# PSU.net
KiCad netlist of a schematic drawn in Altium Designer
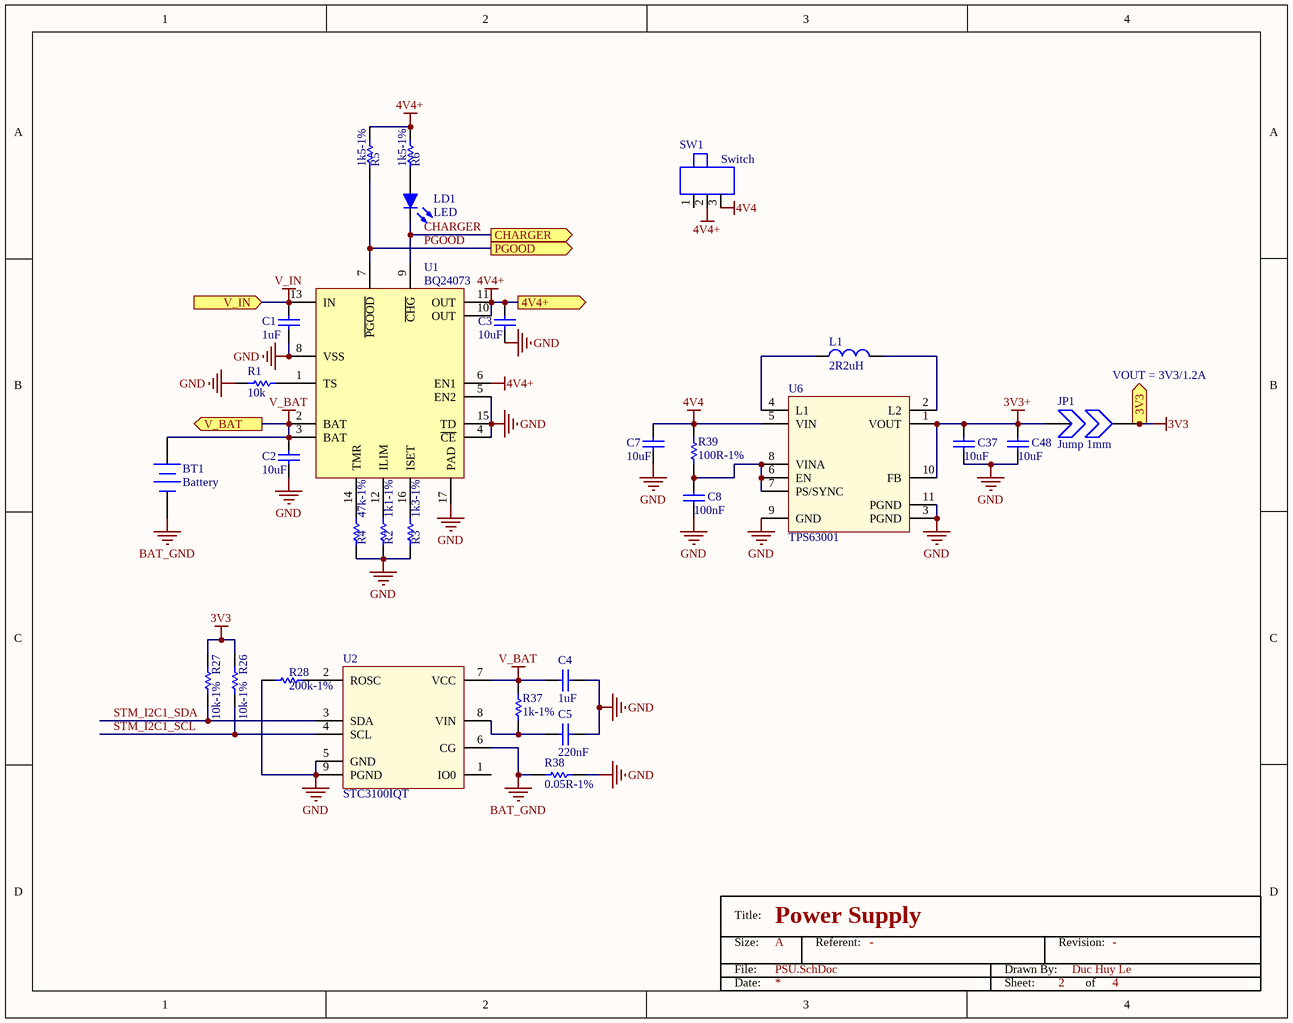
[diagram p0: PSU.SchDoc]

(export (version "E")
  (design (tool "Eeschema 10.0.6"))
  (components
    (comp (ref "BT1")
      (value "Battery")
      (footprint "BAT-2")
      (description "Multicell Battery")
      (fields (field (name "PUBLISHER") "Altium Limited"))
      (libsource (lib "Miscellaneous Devices") (part "Battery"))
    )
    (comp (ref "C1")
      (value "1uF")
      (footprint "Cap 0603")
      (description "Cap SMD")
      (libsource (lib "duchuylee") (part "Cap"))
    )
    (comp (ref "C2")
      (value "10uF")
      (footprint "Cap 0603")
      (description "Cap SMD")
      (libsource (lib "duchuylee") (part "Cap"))
    )
    (comp (ref "C3")
      (value "10uF")
      (footprint "Cap 0603")
      (description "Cap SMD")
      (libsource (lib "duchuylee") (part "Cap"))
    )
    (comp (ref "C4")
      (value "1uF")
      (footprint "Cap 0603")
      (description "Cap SMD")
      (libsource (lib "duchuylee") (part "Cap"))
    )
    (comp (ref "C5")
      (value "220nF")
      (footprint "Cap 0603")
      (description "Cap SMD")
      (libsource (lib "duchuylee") (part "Cap"))
    )
    (comp (ref "C7")
      (value "10uF")
      (footprint "Cap 0603")
      (description "Cap SMD")
      (libsource (lib "duchuylee") (part "Cap"))
    )
    (comp (ref "C8")
      (value "100nF")
      (footprint "Cap 0603")
      (description "Cap SMD")
      (libsource (lib "duchuylee") (part "Cap"))
    )
    (comp (ref "C37")
      (value "10uF")
      (footprint "Cap 0603")
      (description "Cap SMD")
      (libsource (lib "duchuylee") (part "Cap"))
    )
    (comp (ref "C48")
      (value "10uF")
      (footprint "Cap 0603")
      (description "Cap SMD")
      (libsource (lib "duchuylee") (part "Cap"))
    )
    (comp (ref "JP1") (value "Jump 1mm") (footprint "Jump 1mm") (libsource (lib "duchuylee") (part "Jump")))
    (comp (ref "L1")
      (value "2R2uH")
      (footprint "Inductor 0520")
      (description "L- SMD")
      (libsource (lib "duchuylee") (part "Inductor"))
    )
    (comp (ref "LD1") (value "LED") (footprint "LED") (libsource (lib "duchuylee") (part "LED")))
    (comp (ref "R1")
      (value "10k")
      (footprint "Res 0603")
      (description "Res SMD")
      (libsource (lib "duchuylee") (part "Res"))
    )
    (comp (ref "R2")
      (value "1k1-1%")
      (footprint "Res 0603")
      (description "Res SMD")
      (libsource (lib "duchuylee") (part "Res"))
    )
    (comp (ref "R3")
      (value "1k3-1%")
      (footprint "Res 0603")
      (description "Res SMD")
      (libsource (lib "duchuylee") (part "Res"))
    )
    (comp (ref "R4")
      (value "47k-1%")
      (footprint "Res 0603")
      (description "Res SMD")
      (libsource (lib "duchuylee") (part "Res"))
    )
    (comp (ref "R5")
      (value "1k5-1%")
      (footprint "Res 0603")
      (description "Res SMD")
      (libsource (lib "duchuylee") (part "Res"))
    )
    (comp (ref "R6")
      (value "1k5-1%")
      (footprint "Res 0603")
      (description "Res SMD")
      (libsource (lib "duchuylee") (part "Res"))
    )
    (comp (ref "R26")
      (value "10k-1%")
      (footprint "Res 0603")
      (description "Res SMD")
      (libsource (lib "duchuylee") (part "Res"))
    )
    (comp (ref "R27")
      (value "10k-1%")
      (footprint "Res 0603")
      (description "Res SMD")
      (libsource (lib "duchuylee") (part "Res"))
    )
    (comp (ref "R28")
      (value "200k-1%")
      (footprint "Res 0603")
      (description "Res SMD")
      (libsource (lib "duchuylee") (part "Res"))
    )
    (comp (ref "R37")
      (value "1k-1%")
      (footprint "Res 0603")
      (description "Res SMD")
      (libsource (lib "duchuylee") (part "Res"))
    )
    (comp (ref "R38")
      (value "0.05R-1%")
      (footprint "Res 2512")
      (description "Res SMD")
      (libsource (lib "duchuylee") (part "Res"))
    )
    (comp (ref "R39")
      (value "100R-1%")
      (footprint "Res 0603")
      (description "Res SMD")
      (libsource (lib "duchuylee") (part "Res"))
    )
    (comp (ref "SW1")
      (value "Switch")
      (footprint "Slide switch MSK-38")
      (description "MSK-38 Slide switch 3 pin")
      (libsource (lib "duchuylee") (part "SW 3"))
    )
    (comp (ref "TitleBlock2")
      (value "Title Block")
      (fields
        (field (name "REVISION") "-")
        (field (name "TITLE") "Power Supply")
        (field (name "REFERENT") "-")
        (field (name "SIZE") "A")
      )
      (libsource (lib "duchuylee") (part "Title Block"))
    )
    (comp (ref "U1")
      (value "BQ24073")
      (footprint "QFN-16")
      (description "Li-Ion Battery Charger")
      (libsource (lib "duchuylee") (part "BQ24073"))
    )
    (comp (ref "U2")
      (value "STC3100IQT")
      (footprint "DFN-8 3x3")
      (description "Battery monitor IC with Coulomb counter/gas gauge")
      (libsource (lib "duchuylee") (part "STC3100"))
    )
    (comp (ref "U6")
      (value "TPS63001")
      (footprint "VSON-10 3x3")
      (description "TPS6300x High-Efficient Single Inductor Buck-Boost Converter With 1.8-A Switches")
      (libsource (lib "duchuylee") (part "TPS63001"))
    )
  )
  (nets
    (net (code "1") (name "/CHARGER") (class "Default")
      (node (ref "LD1") (pin "2") (pinfunction "K_2") (pintype "passive"))
      (node (ref "U1") (pin "9") (pinfunction "~{CHG}_9") (pintype "passive"))
    )
    (net (code "2") (name "/PGOOD") (class "Default")
      (node (ref "R5") (pin "1") (pinfunction "1_1") (pintype "passive"))
      (node (ref "U1") (pin "7") (pinfunction "~{PGOOD}_7") (pintype "passive"))
    )
    (net (code "3") (name "/STM_I2C1_SCL") (class "Default")
      (node (ref "R26") (pin "2") (pinfunction "2_2") (pintype "passive"))
      (node (ref "U2") (pin "4") (pinfunction "SCL_4") (pintype "passive"))
    )
    (net (code "4") (name "/STM_I2C1_SDA") (class "Default")
      (node (ref "R27") (pin "2") (pinfunction "2_2") (pintype "passive"))
      (node (ref "U2") (pin "3") (pinfunction "SDA_3") (pintype "passive"))
    )
    (net (code "5") (name "3V3") (class "Default")
      (node (ref "JP1") (pin "2") (pinfunction "1_2") (pintype "passive"))
      (node (ref "R26") (pin "1") (pinfunction "1_1") (pintype "passive"))
      (node (ref "R27") (pin "1") (pinfunction "1_1") (pintype "passive"))
    )
    (net (code "6") (name "3V3+") (class "Default")
      (node (ref "C37") (pin "2") (pinfunction "2_2") (pintype "passive"))
      (node (ref "C48") (pin "2") (pinfunction "2_2") (pintype "passive"))
      (node (ref "JP1") (pin "1") (pinfunction "1_1") (pintype "passive"))
      (node (ref "U6") (pin "1") (pinfunction "VOUT_1") (pintype "passive"))
      (node (ref "U6") (pin "10") (pinfunction "FB_10") (pintype "passive"))
    )
    (net (code "7") (name "4V4") (class "Default")
      (node (ref "C7") (pin "2") (pinfunction "2_2") (pintype "passive"))
      (node (ref "R39") (pin "2") (pinfunction "2_2") (pintype "passive"))
      (node (ref "SW1") (pin "3") (pinfunction "A3_3") (pintype "passive"))
      (node (ref "U6") (pin "5") (pinfunction "VIN_5") (pintype "passive"))
    )
    (net (code "8") (name "4V4+") (class "Default")
      (node (ref "C3") (pin "2") (pinfunction "2_2") (pintype "passive"))
      (node (ref "R5") (pin "2") (pinfunction "2_2") (pintype "passive"))
      (node (ref "R6") (pin "2") (pinfunction "2_2") (pintype "passive"))
      (node (ref "SW1") (pin "2") (pinfunction "A2_2") (pintype "passive"))
      (node (ref "U1") (pin "10") (pinfunction "OUT_10") (pintype "passive"))
      (node (ref "U1") (pin "11") (pinfunction "OUT_11") (pintype "passive"))
      (node (ref "U1") (pin "6") (pinfunction "EN1_6") (pintype "passive"))
    )
    (net (code "9") (name "BAT_GND") (class "Default")
      (node (ref "BT1") (pin "2") (pinfunction "-_2") (pintype "passive"))
      (node (ref "R38") (pin "1") (pinfunction "1_1") (pintype "passive"))
      (node (ref "U2") (pin "6") (pinfunction "CG_6") (pintype "passive"))
    )
    (net (code "10") (name "GND") (class "Default")
      (node (ref "C1") (pin "1") (pinfunction "1_1") (pintype "passive"))
      (node (ref "C2") (pin "1") (pinfunction "1_1") (pintype "passive"))
      (node (ref "C3") (pin "1") (pinfunction "1_1") (pintype "passive"))
      (node (ref "C37") (pin "1") (pinfunction "1_1") (pintype "passive"))
      (node (ref "C4") (pin "1") (pinfunction "1_1") (pintype "passive"))
      (node (ref "C48") (pin "1") (pinfunction "1_1") (pintype "passive"))
      (node (ref "C5") (pin "1") (pinfunction "1_1") (pintype "passive"))
      (node (ref "C7") (pin "1") (pinfunction "1_1") (pintype "passive"))
      (node (ref "C8") (pin "1") (pinfunction "1_1") (pintype "passive"))
      (node (ref "R1") (pin "1") (pinfunction "1_1") (pintype "passive"))
      (node (ref "R2") (pin "1") (pinfunction "1_1") (pintype "passive"))
      (node (ref "R28") (pin "1") (pinfunction "1_1") (pintype "passive"))
      (node (ref "R3") (pin "1") (pinfunction "1_1") (pintype "passive"))
      (node (ref "R38") (pin "2") (pinfunction "2_2") (pintype "passive"))
      (node (ref "R4") (pin "1") (pinfunction "1_1") (pintype "passive"))
      (node (ref "U1") (pin "15") (pinfunction "TD_15") (pintype "passive"))
      (node (ref "U1") (pin "17") (pinfunction "PAD_17") (pintype "passive"))
      (node (ref "U1") (pin "4") (pinfunction "~{CE}_4") (pintype "passive"))
      (node (ref "U1") (pin "5") (pinfunction "EN2_5") (pintype "passive"))
      (node (ref "U1") (pin "8") (pinfunction "VSS_8") (pintype "passive"))
      (node (ref "U2") (pin "5") (pinfunction "GND_5") (pintype "passive"))
      (node (ref "U2") (pin "9") (pinfunction "PGND_9") (pintype "passive"))
      (node (ref "U6") (pin "11") (pinfunction "PGND_11") (pintype "passive"))
      (node (ref "U6") (pin "3") (pinfunction "PGND_3") (pintype "passive"))
      (node (ref "U6") (pin "9") (pinfunction "GND_9") (pintype "passive"))
    )
    (net (code "11") (name "Net-(LD1-A)") (class "Default")
      (node (ref "LD1") (pin "1") (pinfunction "A_1") (pintype "passive"))
      (node (ref "R6") (pin "1") (pinfunction "1_1") (pintype "passive"))
    )
    (net (code "12") (name "Net-(U1-ILIM)") (class "Default")
      (node (ref "R2") (pin "2") (pinfunction "2_2") (pintype "passive"))
      (node (ref "U1") (pin "12") (pinfunction "ILIM_12") (pintype "passive"))
    )
    (net (code "13") (name "Net-(U1-ISET)") (class "Default")
      (node (ref "R3") (pin "2") (pinfunction "2_2") (pintype "passive"))
      (node (ref "U1") (pin "16") (pinfunction "ISET_16") (pintype "passive"))
    )
    (net (code "14") (name "Net-(U1-TMR)") (class "Default")
      (node (ref "R4") (pin "2") (pinfunction "2_2") (pintype "passive"))
      (node (ref "U1") (pin "14") (pinfunction "TMR_14") (pintype "passive"))
    )
    (net (code "15") (name "Net-(U1-TS)") (class "Default")
      (node (ref "R1") (pin "2") (pinfunction "2_2") (pintype "passive"))
      (node (ref "U1") (pin "1") (pinfunction "TS_1") (pintype "passive"))
    )
    (net (code "16") (name "Net-(U2-ROSC)") (class "Default")
      (node (ref "R28") (pin "2") (pinfunction "2_2") (pintype "passive"))
      (node (ref "U2") (pin "2") (pinfunction "ROSC_2") (pintype "passive"))
    )
    (net (code "17") (name "Net-(U2-VIN)") (class "Default")
      (node (ref "C5") (pin "2") (pinfunction "2_2") (pintype "passive"))
      (node (ref "R37") (pin "1") (pinfunction "1_1") (pintype "passive"))
      (node (ref "U2") (pin "8") (pinfunction "VIN_8") (pintype "passive"))
    )
    (net (code "18") (name "Net-(U6-EN)") (class "Default")
      (node (ref "C8") (pin "2") (pinfunction "2_2") (pintype "passive"))
      (node (ref "R39") (pin "1") (pinfunction "1_1") (pintype "passive"))
      (node (ref "U6") (pin "6") (pinfunction "EN_6") (pintype "passive"))
      (node (ref "U6") (pin "7") (pinfunction "PS/SYNC_7") (pintype "passive"))
      (node (ref "U6") (pin "8") (pinfunction "VINA_8") (pintype "passive"))
    )
    (net (code "19") (name "Net-(U6-L1)") (class "Default")
      (node (ref "L1") (pin "1") (pinfunction "1_1") (pintype "passive"))
      (node (ref "U6") (pin "4") (pinfunction "L1_4") (pintype "passive"))
    )
    (net (code "20") (name "Net-(U6-L2)") (class "Default")
      (node (ref "L1") (pin "2") (pinfunction "2_2") (pintype "passive"))
      (node (ref "U6") (pin "2") (pinfunction "L2_2") (pintype "passive"))
    )
    (net (code "21") (name "V_BAT") (class "Default")
      (node (ref "BT1") (pin "1") (pinfunction "+_1") (pintype "passive"))
      (node (ref "C2") (pin "2") (pinfunction "2_2") (pintype "passive"))
      (node (ref "C4") (pin "2") (pinfunction "2_2") (pintype "passive"))
      (node (ref "R37") (pin "2") (pinfunction "2_2") (pintype "passive"))
      (node (ref "U1") (pin "2") (pinfunction "BAT_2") (pintype "passive"))
      (node (ref "U1") (pin "3") (pinfunction "BAT_3") (pintype "passive"))
      (node (ref "U2") (pin "7") (pinfunction "VCC_7") (pintype "passive"))
    )
    (net (code "22") (name "V_IN") (class "Default")
      (node (ref "C1") (pin "2") (pinfunction "2_2") (pintype "passive"))
      (node (ref "U1") (pin "13") (pinfunction "IN_13") (pintype "passive"))
    )
    (net (code "23") (name "unconnected-(SW1-A1-Pad1)") (class "Default")
      (node (ref "SW1") (pin "1") (pinfunction "A1_1") (pintype "passive"))
    )
    (net (code "24") (name "unconnected-(U2-IO0-Pad1)") (class "Default")
      (node (ref "U2") (pin "1") (pinfunction "IO0_1") (pintype "passive"))
    )
  )
)
